# 4_IMU.net
KiCad netlist of a schematic drawn in Altium Designer
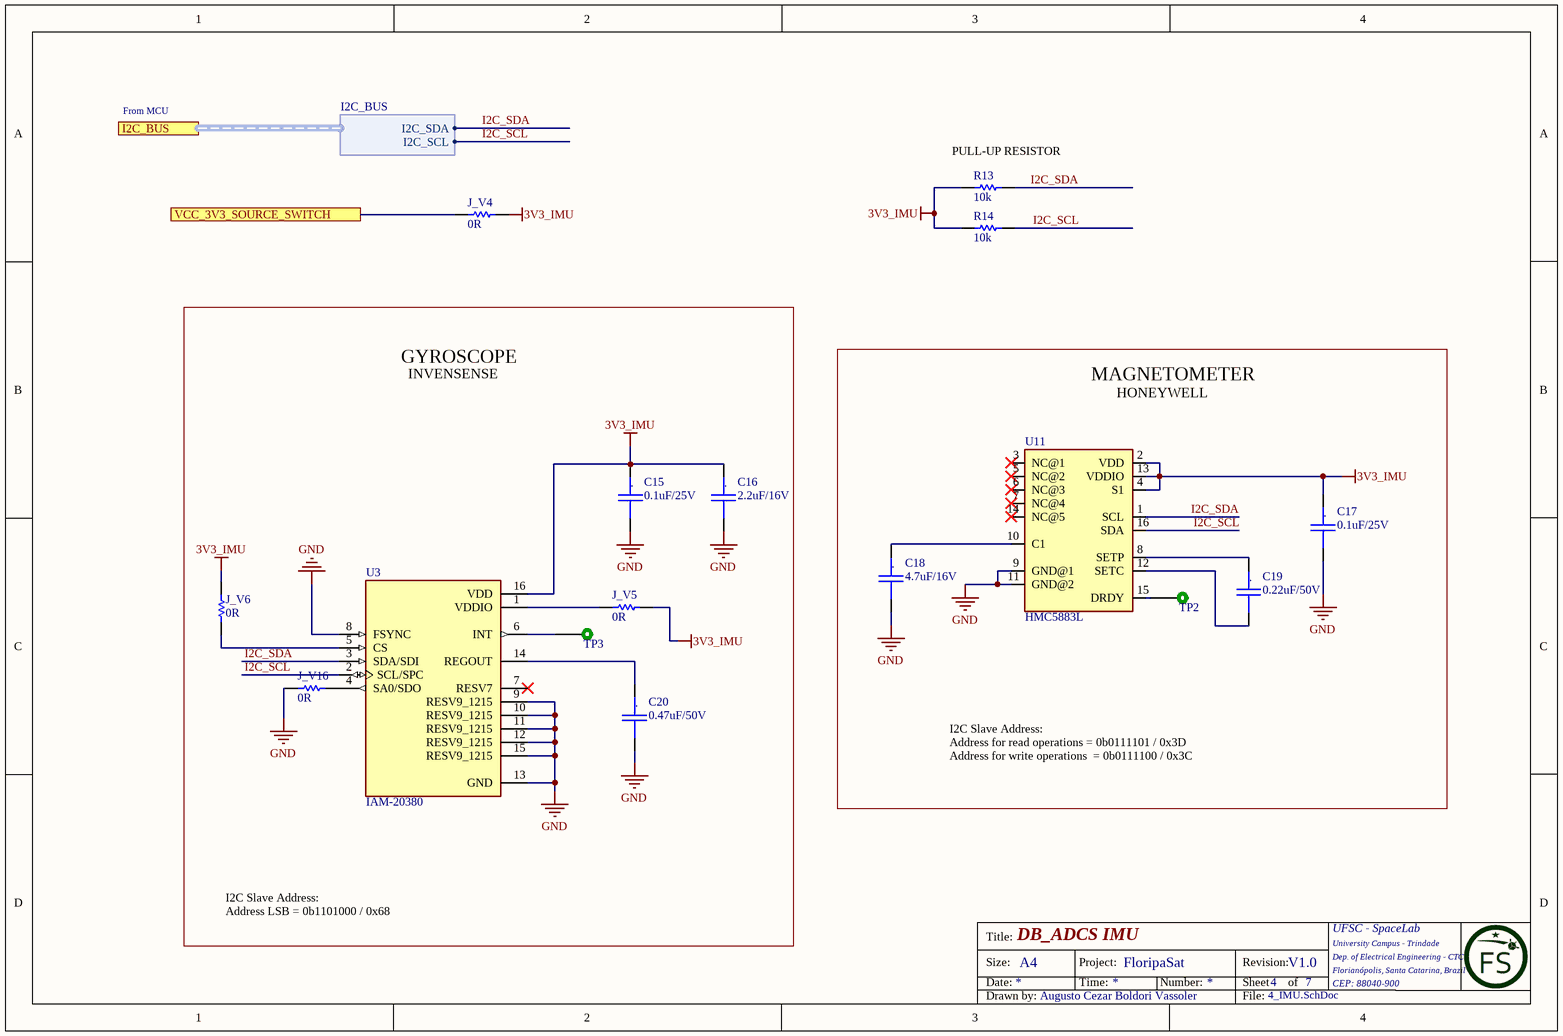
[diagram p0: 4_IMU.SchDoc]

(export (version "E")
  (design (tool "Eeschema 10.0.6"))
  (components
    (comp (ref "C15")
      (value "0.1uF/25V")
      (footprint "CC0805")
      (description "CAP CER 0.1UF 25V 10% X7R 0805")
      (fields (field (name "PARTNUMBER") "CC0805KRX7R8BB104"))
      (libsource (lib "PCB_Eng_Model_OBDH_2") (part "Cap_Cer_X7R_0.1uF_25V_0805"))
    )
    (comp (ref "C16")
      (value "2.2uF/16V")
      (footprint "CC0805")
      (description "CAP CER 2.2uF 16V 0805")
      (fields (field (name "PARTNUMBER") "C2012X7R1C225K125AB"))
      (libsource (lib "PCB_Eng_Model_OBDH_2") (part "Cap_Cer_X7R_2.2uF_16V_0805"))
    )
    (comp (ref "C17")
      (value "0.1uF/25V")
      (footprint "CC0805")
      (description "CAP CER 0.1UF 25V 10% X7R 0805")
      (fields (field (name "PARTNUMBER") "CC0805KRX7R8BB104"))
      (libsource (lib "PCB_Eng_Model_OBDH_2") (part "Cap_Cer_X7R_0.1uF_25V_0805"))
    )
    (comp (ref "C18")
      (value "4.7uF/16V")
      (footprint "CC0805")
      (description "Cap Ceramic 4.7uF 16V X7R 10% SMD 0805 125C Embossed T/R")
      (fields
        (field (name "MANUFACTURER") "Kyocera AVX")
        (field (name "MANUFACTURER PART NUMBER") "0805YC475KAT2A")
      )
      (libsource (lib "PCB_Eng_Model_OBDH_2") (part "Cap_Cer_X7R_4.7uF_16V_0805"))
    )
    (comp (ref "C19")
      (value "0.22uF/50V")
      (footprint "CC0805")
      (description "CAP CER 0.22UF 50V X7R 0805")
      (fields
        (field (name "MANUFACTURER") "KEMET")
        (field (name "MANUFACTURER PART NUMBER") "C0805C224K5RACTU")
      )
      (libsource (lib "PCB_Eng_Model_OBDH_2") (part "Cap_Cer_X7R_0.22uF_0805"))
    )
    (comp (ref "C20")
      (value "0.47uF/50V")
      (footprint "CC0805")
      (description "CAP CER 0.47UF 50V 10% X7R 0805")
      (fields (field (name "PARTNUMBER") "C0805C474K5RACTU"))
      (libsource (lib "PCB_Eng_Model_OBDH_2") (part "Cap_Cer_X7R_0.47uF_50V_0805"))
    )
    (comp (ref "J_V4")
      (value "0R")
      (footprint "0805-LED")
      (description "RES 0R OHM 1/16W JUMPER 0805")
      (fields (field (name "PARTNUMBER") "CRCW08050000Z0EA"))
      (libsource (lib "PCB_Eng_Model_OBDH_2") (part "R0R_JUMPER_1/16W_0805"))
    )
    (comp (ref "J_V5")
      (value "0R")
      (footprint "0805-LED")
      (description "RES 0R OHM 1/16W JUMPER 0805")
      (fields (field (name "PARTNUMBER") "CRCW08050000Z0EA"))
      (libsource (lib "PCB_Eng_Model_OBDH_2") (part "R0R_JUMPER_1/16W_0805"))
    )
    (comp (ref "J_V6")
      (value "0R")
      (footprint "0805-LED")
      (description "RES 0R OHM 1/16W JUMPER 0805")
      (fields (field (name "PARTNUMBER") "CRCW08050000Z0EA"))
      (libsource (lib "PCB_Eng_Model_OBDH_2") (part "R0R_JUMPER_1/16W_0805"))
    )
    (comp (ref "J_V16")
      (value "0R")
      (footprint "0805-LED")
      (description "RES 0R OHM 1/16W JUMPER 0805")
      (fields (field (name "PARTNUMBER") "CRCW08050000Z0EA"))
      (libsource (lib "PCB_Eng_Model_OBDH_2") (part "R0R_JUMPER_1/16W_0805"))
    )
    (comp (ref "R13")
      (value "10k")
      (footprint "0805")
      (description "RES 10K OHM 1/8W 1%  0805")
      (fields (field (name "PARTNUMBER") "CRCW080510K0FKEA"))
      (libsource (lib "PCB_Eng_Model_OBDH_2") (part "R10k_1%_1/8W_0805"))
    )
    (comp (ref "R14")
      (value "10k")
      (footprint "0805")
      (description "RES 10K OHM 1/8W 1%  0805")
      (fields (field (name "PARTNUMBER") "CRCW080510K0FKEA"))
      (libsource (lib "PCB_Eng_Model_OBDH_2") (part "R10k_1%_1/8W_0805"))
    )
    (comp (ref "TP2")
      (value "TEST_POINT_2")
      (footprint "TEST_POINT_2")
      (description "Test point")
      (libsource (lib "PCB_Eng_Model_OBDH_2") (part "TEST_POINT_2"))
    )
    (comp (ref "TP3")
      (value "TEST_POINT_2")
      (footprint "TEST_POINT_2")
      (description "Test point")
      (libsource (lib "PCB_Eng_Model_OBDH_2") (part "TEST_POINT_2"))
    )
    (comp (ref "U3")
      (value "IAM-20380")
      (footprint "PQFN50P300X300X80-16N")
      (description "Gyroscope X _Pitch_, Y _Roll_, Z _Yaw_ Â±250, 500, 1000, 2000 27kHz IÂ²C, SPI 16-LGA _3x3_")
      (fields (field (name "MF") "TDK InvenSense"))
      (libsource (lib "IAM-20380") (part "IAM-20380"))
    )
    (comp (ref "U11")
      (value "HMC5883L")
      (footprint "LPCC-16")
      (description "Magnetoresistive Sensor X, Y, Z Axis 16-LCC")
      (fields (field (name "MF") "Honeywell") (field (name "MP") "HMC5883L-T"))
      (libsource (lib "HMC5883L") (part "HMC5883L"))
    )
  )
  (nets
    (net (code "2") (name "/I2C_SCL") (class "Default")
      (node (ref "R14") (pin "1") (pinfunction "1_1") (pintype "passive"))
      (node (ref "U11") (pin "16") (pinfunction "SDA_16") (pintype "bidirectional"))
      (node (ref "U3") (pin "2") (pinfunction "SCL/SPC_2") (pintype "bidirectional"))
    )
    (net (code "3") (name "/I2C_SDA") (class "Default")
      (node (ref "R13") (pin "1") (pinfunction "1_1") (pintype "passive"))
      (node (ref "U11") (pin "1") (pinfunction "SCL_1") (pintype "bidirectional"))
      (node (ref "U3") (pin "3") (pinfunction "SDA/SDI_3") (pintype "input"))
    )
    (net (code "4") (name "/VCC_3V3_SOURCE_SWITCH") (class "Default")
      (node (ref "J_V4") (pin "2") (pinfunction "2_2") (pintype "passive"))
    )
    (net (code "6") (name "3V3_IMU") (class "Default")
      (node (ref "C15") (pin "1") (pinfunction "1_1") (pintype "passive"))
      (node (ref "C16") (pin "1") (pinfunction "1_1") (pintype "passive"))
      (node (ref "C17") (pin "1") (pinfunction "1_1") (pintype "passive"))
      (node (ref "J_V4") (pin "1") (pinfunction "1_1") (pintype "passive"))
      (node (ref "J_V5") (pin "1") (pinfunction "1_1") (pintype "passive"))
      (node (ref "J_V6") (pin "2") (pinfunction "2_2") (pintype "passive"))
      (node (ref "R13") (pin "2") (pinfunction "2_2") (pintype "passive"))
      (node (ref "R14") (pin "2") (pinfunction "2_2") (pintype "passive"))
      (node (ref "U11") (pin "13") (pinfunction "VDDIO_13") (pintype "bidirectional"))
      (node (ref "U11") (pin "2") (pinfunction "VDD_2") (pintype "bidirectional"))
      (node (ref "U11") (pin "4") (pinfunction "S1_4") (pintype "bidirectional"))
      (node (ref "U3") (pin "16") (pinfunction "VDD_16") (pintype "power_in"))
    )
    (net (code "7") (name "GND") (class "Default")
      (node (ref "C15") (pin "2") (pinfunction "2_2") (pintype "passive"))
      (node (ref "C16") (pin "2") (pinfunction "2_2") (pintype "passive"))
      (node (ref "C17") (pin "2") (pinfunction "2_2") (pintype "passive"))
      (node (ref "C18") (pin "2") (pinfunction "2_2") (pintype "passive"))
      (node (ref "C20") (pin "2") (pinfunction "2_2") (pintype "passive"))
      (node (ref "J_V16") (pin "2") (pinfunction "2_2") (pintype "passive"))
      (node (ref "U11") (pin "11") (pinfunction "GND@2_11") (pintype "bidirectional"))
      (node (ref "U11") (pin "9") (pinfunction "GND@1_9") (pintype "bidirectional"))
      (node (ref "U3") (pin "10") (pinfunction "RESV9_1215_10") (pintype "passive"))
      (node (ref "U3") (pin "11") (pinfunction "RESV9_1215_11") (pintype "passive"))
      (node (ref "U3") (pin "12") (pinfunction "RESV9_1215_12") (pintype "passive"))
      (node (ref "U3") (pin "13") (pinfunction "GND_13") (pintype "power_in"))
      (node (ref "U3") (pin "15") (pinfunction "RESV9_1215_15") (pintype "passive"))
      (node (ref "U3") (pin "8") (pinfunction "FSYNC_8") (pintype "input"))
      (node (ref "U3") (pin "9") (pinfunction "RESV9_1215_9") (pintype "passive"))
    )
    (net (code "8") (name "Net-(U3-CS)") (class "Default")
      (node (ref "J_V6") (pin "1") (pinfunction "1_1") (pintype "passive"))
      (node (ref "U3") (pin "5") (pinfunction "CS_5") (pintype "input"))
    )
    (net (code "9") (name "Net-(U3-INT)") (class "Default")
      (node (ref "TP3") (pin "1") (pinfunction "1_1") (pintype "passive"))
      (node (ref "U3") (pin "6") (pinfunction "INT_6") (pintype "output"))
    )
    (net (code "10") (name "Net-(U3-REGOUT)") (class "Default")
      (node (ref "C20") (pin "1") (pinfunction "1_1") (pintype "passive"))
      (node (ref "U3") (pin "14") (pinfunction "REGOUT_14") (pintype "passive"))
    )
    (net (code "11") (name "Net-(U3-SA0{slash}SDO)") (class "Default")
      (node (ref "J_V16") (pin "1") (pinfunction "1_1") (pintype "passive"))
      (node (ref "U3") (pin "4") (pinfunction "SA0/SDO_4") (pintype "output"))
    )
    (net (code "12") (name "Net-(U3-VDDIO)") (class "Default")
      (node (ref "J_V5") (pin "2") (pinfunction "2_2") (pintype "passive"))
      (node (ref "U3") (pin "1") (pinfunction "VDDIO_1") (pintype "power_in"))
    )
    (net (code "13") (name "Net-(U11-C1)") (class "Default")
      (node (ref "C18") (pin "1") (pinfunction "1_1") (pintype "passive"))
      (node (ref "U11") (pin "10") (pinfunction "C1_10") (pintype "bidirectional"))
    )
    (net (code "14") (name "Net-(U11-DRDY)") (class "Default")
      (node (ref "TP2") (pin "1") (pinfunction "1_1") (pintype "passive"))
      (node (ref "U11") (pin "15") (pinfunction "DRDY_15") (pintype "bidirectional"))
    )
    (net (code "15") (name "Net-(U11-SETC)") (class "Default")
      (node (ref "C19") (pin "2") (pinfunction "2_2") (pintype "passive"))
      (node (ref "U11") (pin "12") (pinfunction "SETC_12") (pintype "bidirectional"))
    )
    (net (code "16") (name "Net-(U11-SETP)") (class "Default")
      (node (ref "C19") (pin "1") (pinfunction "1_1") (pintype "passive"))
      (node (ref "U11") (pin "8") (pinfunction "SETP_8") (pintype "bidirectional"))
    )
    (net (code "17") (name "unconnected-(U3-RESV7-Pad7)") (class "Default")
      (node (ref "U3") (pin "7") (pinfunction "RESV7_7") (pintype "passive+no_connect"))
    )
    (net (code "18") (name "unconnected-(U11-NC@1-Pad3)") (class "Default")
      (node (ref "U11") (pin "3") (pinfunction "NC@1_3") (pintype "bidirectional+no_connect"))
    )
    (net (code "19") (name "unconnected-(U11-NC@2-Pad5)") (class "Default")
      (node (ref "U11") (pin "5") (pinfunction "NC@2_5") (pintype "bidirectional+no_connect"))
    )
    (net (code "20") (name "unconnected-(U11-NC@3-Pad6)") (class "Default")
      (node (ref "U11") (pin "6") (pinfunction "NC@3_6") (pintype "bidirectional+no_connect"))
    )
    (net (code "21") (name "unconnected-(U11-NC@4-Pad7)") (class "Default")
      (node (ref "U11") (pin "7") (pinfunction "NC@4_7") (pintype "bidirectional+no_connect"))
    )
    (net (code "22") (name "unconnected-(U11-NC@5-Pad14)") (class "Default")
      (node (ref "U11") (pin "14") (pinfunction "NC@5_14") (pintype "bidirectional+no_connect"))
    )
  )
)
